# bmsSlave_cells.net
KiCad netlist of a schematic drawn in Altium Designer
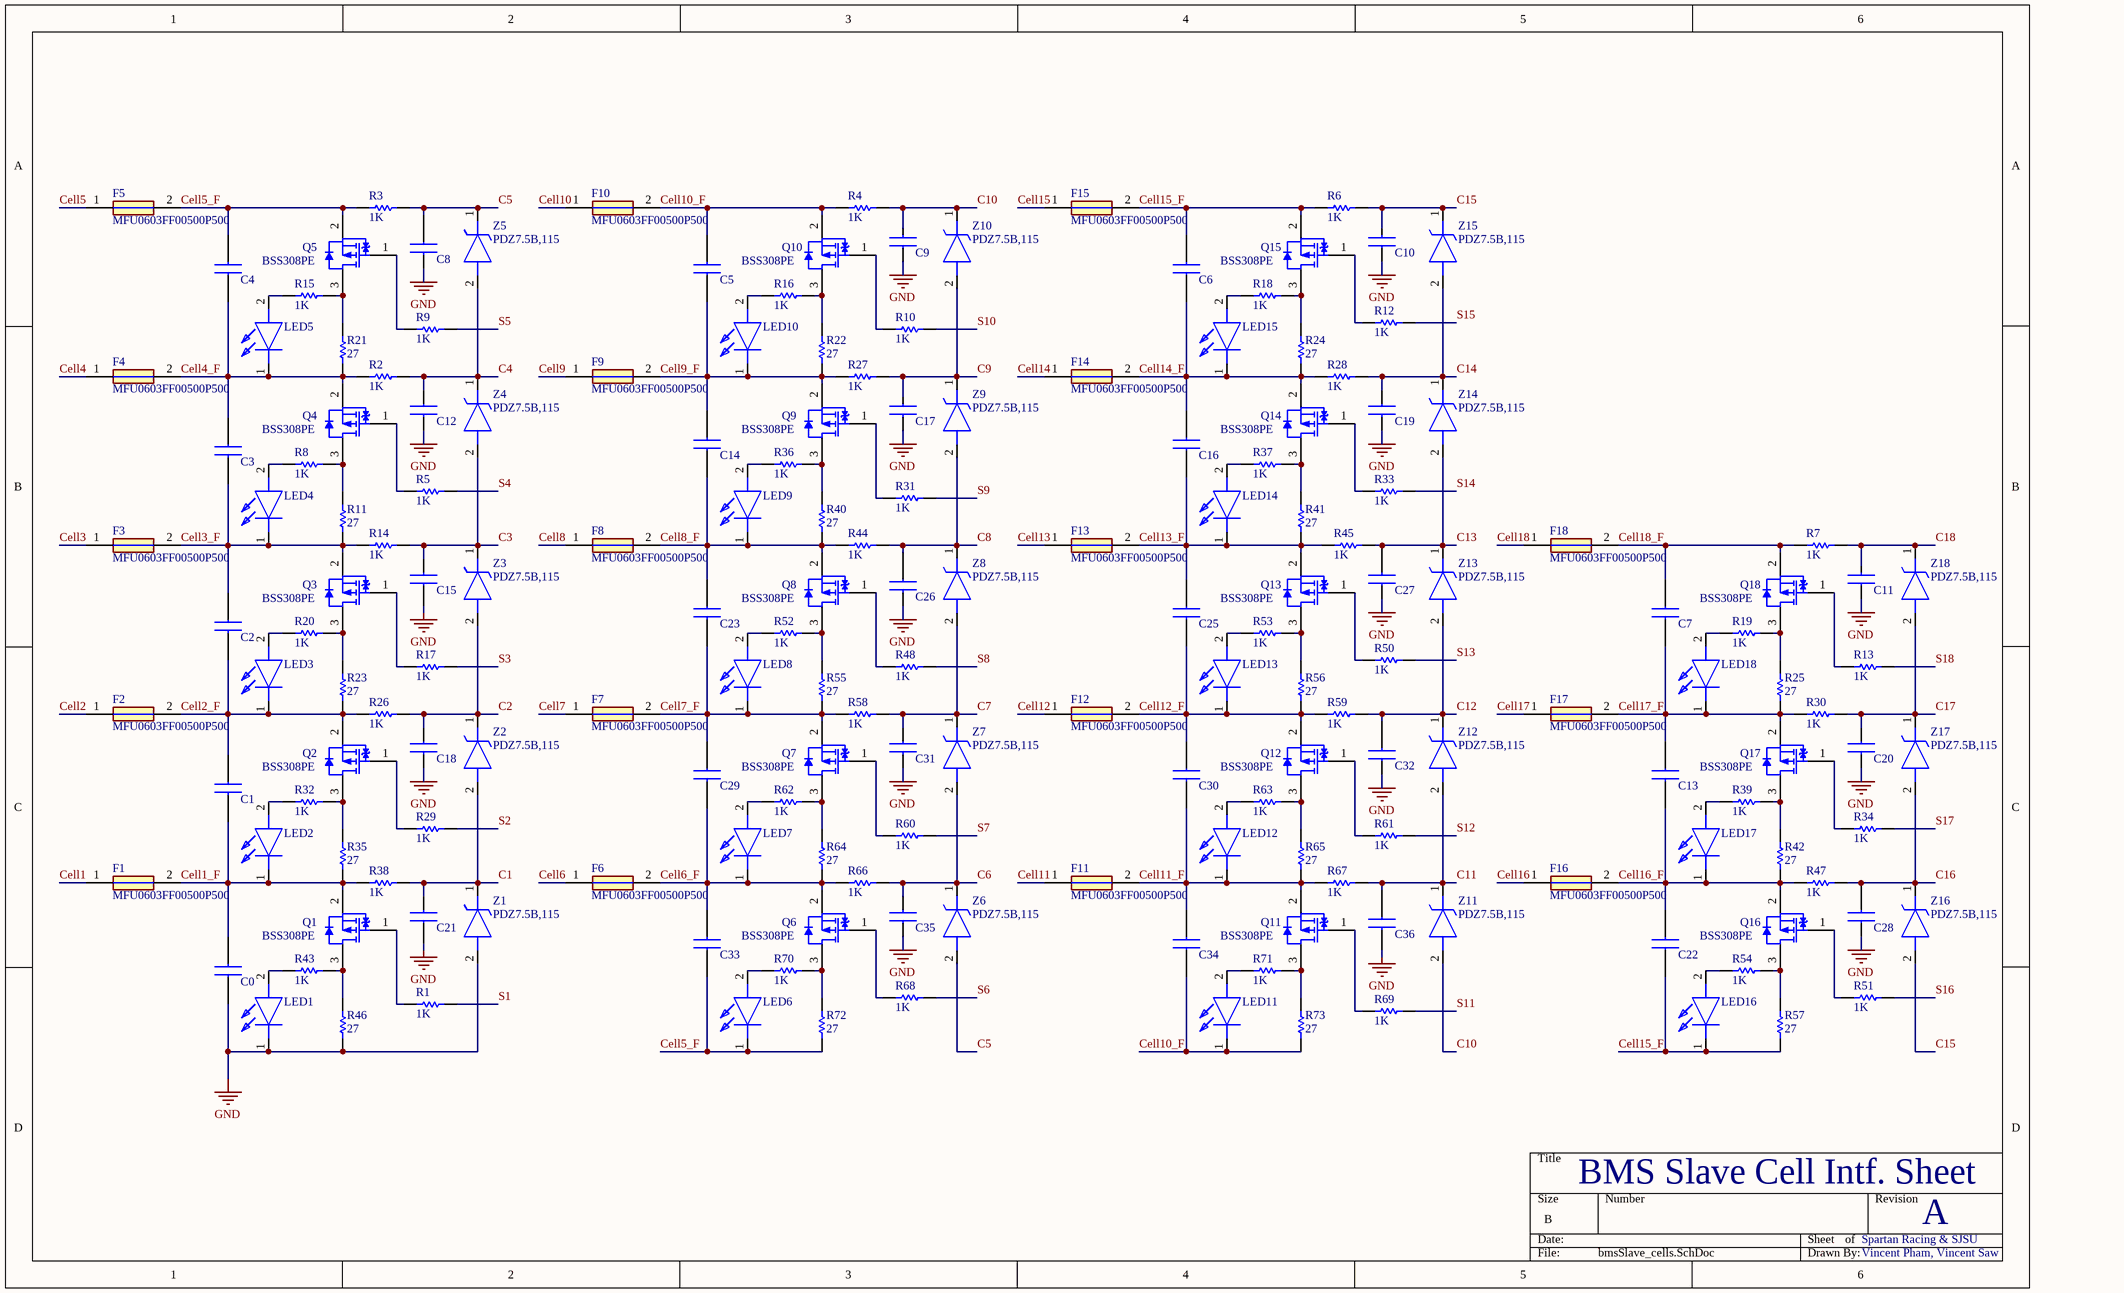
[diagram p0: bmsSlave_cells.SchDoc]

(export (version "E")
  (design (tool "Eeschema 10.0.6"))
  (components
    (comp (ref "C0")
      (value "885382207009")
      (footprint "C0603")
      (description "Multilayer Ceramic Chip Capacitor WCAP-CSST Series 0805 10000pF X7R0805103K100DFCT1S000")
      (fields (field (name "MOUSER PART NUMBER") "710-885382207009"))
      (libsource (lib "885382207009") (part "885382207009"))
    )
    (comp (ref "C1")
      (value "885382207009")
      (footprint "C0603")
      (description "Multilayer Ceramic Chip Capacitor WCAP-CSST Series 0805 10000pF X7R0805103K100DFCT1S000")
      (fields (field (name "MOUSER PART NUMBER") "710-885382207009"))
      (libsource (lib "885382207009") (part "885382207009"))
    )
    (comp (ref "C2")
      (value "885382207009")
      (footprint "C0603")
      (description "Multilayer Ceramic Chip Capacitor WCAP-CSST Series 0805 10000pF X7R0805103K100DFCT1S000")
      (fields (field (name "MOUSER PART NUMBER") "710-885382207009"))
      (libsource (lib "885382207009") (part "885382207009"))
    )
    (comp (ref "C3")
      (value "885382207009")
      (footprint "C0603")
      (description "Multilayer Ceramic Chip Capacitor WCAP-CSST Series 0805 10000pF X7R0805103K100DFCT1S000")
      (fields (field (name "MOUSER PART NUMBER") "710-885382207009"))
      (libsource (lib "885382207009") (part "885382207009"))
    )
    (comp (ref "C4")
      (value "885382207009")
      (footprint "C0603")
      (description "Multilayer Ceramic Chip Capacitor WCAP-CSST Series 0805 10000pF X7R0805103K100DFCT1S000")
      (fields (field (name "MOUSER PART NUMBER") "710-885382207009"))
      (libsource (lib "885382207009") (part "885382207009"))
    )
    (comp (ref "C5")
      (value "885382207009")
      (footprint "C0603")
      (description "Multilayer Ceramic Chip Capacitor WCAP-CSST Series 0805 10000pF X7R0805103K100DFCT1S000")
      (fields (field (name "MOUSER PART NUMBER") "710-885382207009"))
      (libsource (lib "885382207009") (part "885382207009"))
    )
    (comp (ref "C6")
      (value "885382207009")
      (footprint "C0603")
      (description "Multilayer Ceramic Chip Capacitor WCAP-CSST Series 0805 10000pF X7R0805103K100DFCT1S000")
      (fields (field (name "MOUSER PART NUMBER") "710-885382207009"))
      (libsource (lib "885382207009") (part "885382207009"))
    )
    (comp (ref "C7")
      (value "885382207009")
      (footprint "C0603")
      (description "Multilayer Ceramic Chip Capacitor WCAP-CSST Series 0805 10000pF X7R0805103K100DFCT1S000")
      (fields (field (name "MOUSER PART NUMBER") "710-885382207009"))
      (libsource (lib "885382207009") (part "885382207009"))
    )
    (comp (ref "C8")
      (value "885382207009")
      (footprint "C0603")
      (description "Multilayer Ceramic Chip Capacitor WCAP-CSST Series 0805 10000pF X7R0805103K100DFCT1S000")
      (fields (field (name "MOUSER PART NUMBER") "710-885382207009"))
      (libsource (lib "885382207009") (part "885382207009"))
    )
    (comp (ref "C9")
      (value "885382207009")
      (footprint "C0603")
      (description "Multilayer Ceramic Chip Capacitor WCAP-CSST Series 0805 10000pF X7R0805103K100DFCT1S000")
      (fields (field (name "MOUSER PART NUMBER") "710-885382207009"))
      (libsource (lib "885382207009") (part "885382207009"))
    )
    (comp (ref "C10")
      (value "885382207009")
      (footprint "C0603")
      (description "Multilayer Ceramic Chip Capacitor WCAP-CSST Series 0805 10000pF X7R0805103K100DFCT1S000")
      (fields (field (name "MOUSER PART NUMBER") "710-885382207009"))
      (libsource (lib "885382207009") (part "885382207009"))
    )
    (comp (ref "C11")
      (value "885382207009")
      (footprint "C0603")
      (description "Multilayer Ceramic Chip Capacitor WCAP-CSST Series 0805 10000pF X7R0805103K100DFCT1S000")
      (fields (field (name "MOUSER PART NUMBER") "710-885382207009"))
      (libsource (lib "885382207009") (part "885382207009"))
    )
    (comp (ref "C12")
      (value "885382207009")
      (footprint "C0603")
      (description "Multilayer Ceramic Chip Capacitor WCAP-CSST Series 0805 10000pF X7R0805103K100DFCT1S000")
      (fields (field (name "MOUSER PART NUMBER") "710-885382207009"))
      (libsource (lib "885382207009") (part "885382207009"))
    )
    (comp (ref "C13")
      (value "885382207009")
      (footprint "C0603")
      (description "Multilayer Ceramic Chip Capacitor WCAP-CSST Series 0805 10000pF X7R0805103K100DFCT1S000")
      (fields (field (name "MOUSER PART NUMBER") "710-885382207009"))
      (libsource (lib "885382207009") (part "885382207009"))
    )
    (comp (ref "C14")
      (value "885382207009")
      (footprint "C0603")
      (description "Multilayer Ceramic Chip Capacitor WCAP-CSST Series 0805 10000pF X7R0805103K100DFCT1S000")
      (fields (field (name "MOUSER PART NUMBER") "710-885382207009"))
      (libsource (lib "885382207009") (part "885382207009"))
    )
    (comp (ref "C15")
      (value "885382207009")
      (footprint "C0603")
      (description "Multilayer Ceramic Chip Capacitor WCAP-CSST Series 0805 10000pF X7R0805103K100DFCT1S000")
      (fields (field (name "MOUSER PART NUMBER") "710-885382207009"))
      (libsource (lib "885382207009") (part "885382207009"))
    )
    (comp (ref "C16")
      (value "885382207009")
      (footprint "C0603")
      (description "Multilayer Ceramic Chip Capacitor WCAP-CSST Series 0805 10000pF X7R0805103K100DFCT1S000")
      (fields (field (name "MOUSER PART NUMBER") "710-885382207009"))
      (libsource (lib "885382207009") (part "885382207009"))
    )
    (comp (ref "C17")
      (value "885382207009")
      (footprint "C0603")
      (description "Multilayer Ceramic Chip Capacitor WCAP-CSST Series 0805 10000pF X7R0805103K100DFCT1S000")
      (fields (field (name "MOUSER PART NUMBER") "710-885382207009"))
      (libsource (lib "885382207009") (part "885382207009"))
    )
    (comp (ref "C18")
      (value "885382207009")
      (footprint "C0603")
      (description "Multilayer Ceramic Chip Capacitor WCAP-CSST Series 0805 10000pF X7R0805103K100DFCT1S000")
      (fields (field (name "MOUSER PART NUMBER") "710-885382207009"))
      (libsource (lib "885382207009") (part "885382207009"))
    )
    (comp (ref "C19")
      (value "885382207009")
      (footprint "C0603")
      (description "Multilayer Ceramic Chip Capacitor WCAP-CSST Series 0805 10000pF X7R0805103K100DFCT1S000")
      (fields (field (name "MOUSER PART NUMBER") "710-885382207009"))
      (libsource (lib "885382207009") (part "885382207009"))
    )
    (comp (ref "C20")
      (value "885382207009")
      (footprint "C0603")
      (description "Multilayer Ceramic Chip Capacitor WCAP-CSST Series 0805 10000pF X7R0805103K100DFCT1S000")
      (fields (field (name "MOUSER PART NUMBER") "710-885382207009"))
      (libsource (lib "885382207009") (part "885382207009"))
    )
    (comp (ref "C21")
      (value "885382207009")
      (footprint "C0603")
      (description "Multilayer Ceramic Chip Capacitor WCAP-CSST Series 0805 10000pF X7R0805103K100DFCT1S000")
      (fields (field (name "MOUSER PART NUMBER") "710-885382207009"))
      (libsource (lib "885382207009") (part "885382207009"))
    )
    (comp (ref "C22")
      (value "885382207009")
      (footprint "C0603")
      (description "Multilayer Ceramic Chip Capacitor WCAP-CSST Series 0805 10000pF X7R0805103K100DFCT1S000")
      (fields (field (name "MOUSER PART NUMBER") "710-885382207009"))
      (libsource (lib "885382207009") (part "885382207009"))
    )
    (comp (ref "C23")
      (value "885382207009")
      (footprint "C0603")
      (description "Multilayer Ceramic Chip Capacitor WCAP-CSST Series 0805 10000pF X7R0805103K100DFCT1S000")
      (fields (field (name "MOUSER PART NUMBER") "710-885382207009"))
      (libsource (lib "885382207009") (part "885382207009"))
    )
    (comp (ref "C25")
      (value "885382207009")
      (footprint "C0603")
      (description "Multilayer Ceramic Chip Capacitor WCAP-CSST Series 0805 10000pF X7R0805103K100DFCT1S000")
      (fields (field (name "MOUSER PART NUMBER") "710-885382207009"))
      (libsource (lib "885382207009") (part "885382207009"))
    )
    (comp (ref "C26")
      (value "885382207009")
      (footprint "C0603")
      (description "Multilayer Ceramic Chip Capacitor WCAP-CSST Series 0805 10000pF X7R0805103K100DFCT1S000")
      (fields (field (name "MOUSER PART NUMBER") "710-885382207009"))
      (libsource (lib "885382207009") (part "885382207009"))
    )
    (comp (ref "C27")
      (value "885382207009")
      (footprint "C0603")
      (description "Multilayer Ceramic Chip Capacitor WCAP-CSST Series 0805 10000pF X7R0805103K100DFCT1S000")
      (fields (field (name "MOUSER PART NUMBER") "710-885382207009"))
      (libsource (lib "885382207009") (part "885382207009"))
    )
    (comp (ref "C28")
      (value "885382207009")
      (footprint "C0603")
      (description "Multilayer Ceramic Chip Capacitor WCAP-CSST Series 0805 10000pF X7R0805103K100DFCT1S000")
      (fields (field (name "MOUSER PART NUMBER") "710-885382207009"))
      (libsource (lib "885382207009") (part "885382207009"))
    )
    (comp (ref "C29")
      (value "885382207009")
      (footprint "C0603")
      (description "Multilayer Ceramic Chip Capacitor WCAP-CSST Series 0805 10000pF X7R0805103K100DFCT1S000")
      (fields (field (name "MOUSER PART NUMBER") "710-885382207009"))
      (libsource (lib "885382207009") (part "885382207009"))
    )
    (comp (ref "C30")
      (value "885382207009")
      (footprint "C0603")
      (description "Multilayer Ceramic Chip Capacitor WCAP-CSST Series 0805 10000pF X7R0805103K100DFCT1S000")
      (fields (field (name "MOUSER PART NUMBER") "710-885382207009"))
      (libsource (lib "885382207009") (part "885382207009"))
    )
    (comp (ref "C31")
      (value "885382207009")
      (footprint "C0603")
      (description "Multilayer Ceramic Chip Capacitor WCAP-CSST Series 0805 10000pF X7R0805103K100DFCT1S000")
      (fields (field (name "MOUSER PART NUMBER") "710-885382207009"))
      (libsource (lib "885382207009") (part "885382207009"))
    )
    (comp (ref "C32")
      (value "885382207009")
      (footprint "C0603")
      (description "Multilayer Ceramic Chip Capacitor WCAP-CSST Series 0805 10000pF X7R0805103K100DFCT1S000")
      (fields (field (name "MOUSER PART NUMBER") "710-885382207009"))
      (libsource (lib "885382207009") (part "885382207009"))
    )
    (comp (ref "C33")
      (value "885382207009")
      (footprint "C0603")
      (description "Multilayer Ceramic Chip Capacitor WCAP-CSST Series 0805 10000pF X7R0805103K100DFCT1S000")
      (fields (field (name "MOUSER PART NUMBER") "710-885382207009"))
      (libsource (lib "885382207009") (part "885382207009"))
    )
    (comp (ref "C34")
      (value "885382207009")
      (footprint "C0603")
      (description "Multilayer Ceramic Chip Capacitor WCAP-CSST Series 0805 10000pF X7R0805103K100DFCT1S000")
      (fields (field (name "MOUSER PART NUMBER") "710-885382207009"))
      (libsource (lib "885382207009") (part "885382207009"))
    )
    (comp (ref "C35")
      (value "885382207009")
      (footprint "C0603")
      (description "Multilayer Ceramic Chip Capacitor WCAP-CSST Series 0805 10000pF X7R0805103K100DFCT1S000")
      (fields (field (name "MOUSER PART NUMBER") "710-885382207009"))
      (libsource (lib "885382207009") (part "885382207009"))
    )
    (comp (ref "C36")
      (value "885382207009")
      (footprint "C0603")
      (description "Multilayer Ceramic Chip Capacitor WCAP-CSST Series 0805 10000pF X7R0805103K100DFCT1S000")
      (fields (field (name "MOUSER PART NUMBER") "710-885382207009"))
      (libsource (lib "885382207009") (part "885382207009"))
    )
    (comp (ref "F1")
      (value "MFU0603FF00500P500")
      (footprint "FUSC1608X55N")
      (description "Fuse")
      (fields (field (name "MOUSER PART NUMBER") "594-MFU0603-FF-0.5"))
      (libsource (lib "bmsSlave") (part "MFU0603FF00500P500"))
    )
    (comp (ref "F2")
      (value "MFU0603FF00500P500")
      (footprint "FUSC1608X55N")
      (description "Fuse")
      (fields (field (name "MOUSER PART NUMBER") "594-MFU0603-FF-0.5"))
      (libsource (lib "bmsSlave") (part "MFU0603FF00500P500"))
    )
    (comp (ref "F3")
      (value "MFU0603FF00500P500")
      (footprint "FUSC1608X55N")
      (description "Fuse")
      (fields (field (name "MOUSER PART NUMBER") "594-MFU0603-FF-0.5"))
      (libsource (lib "bmsSlave") (part "MFU0603FF00500P500"))
    )
    (comp (ref "F4")
      (value "MFU0603FF00500P500")
      (footprint "FUSC1608X55N")
      (description "Fuse")
      (fields (field (name "MOUSER PART NUMBER") "594-MFU0603-FF-0.5"))
      (libsource (lib "bmsSlave") (part "MFU0603FF00500P500"))
    )
    (comp (ref "F5")
      (value "MFU0603FF00500P500")
      (footprint "FUSC1608X55N")
      (description "Fuse")
      (fields (field (name "MOUSER PART NUMBER") "594-MFU0603-FF-0.5"))
      (libsource (lib "bmsSlave") (part "MFU0603FF00500P500"))
    )
    (comp (ref "F6")
      (value "MFU0603FF00500P500")
      (footprint "FUSC1608X55N")
      (description "Fuse")
      (fields (field (name "MOUSER PART NUMBER") "594-MFU0603-FF-0.5"))
      (libsource (lib "bmsSlave") (part "MFU0603FF00500P500"))
    )
    (comp (ref "F7")
      (value "MFU0603FF00500P500")
      (footprint "FUSC1608X55N")
      (description "Fuse")
      (fields (field (name "MOUSER PART NUMBER") "594-MFU0603-FF-0.5"))
      (libsource (lib "bmsSlave") (part "MFU0603FF00500P500"))
    )
    (comp (ref "F8")
      (value "MFU0603FF00500P500")
      (footprint "FUSC1608X55N")
      (description "Fuse")
      (fields (field (name "MOUSER PART NUMBER") "594-MFU0603-FF-0.5"))
      (libsource (lib "bmsSlave") (part "MFU0603FF00500P500"))
    )
    (comp (ref "F9")
      (value "MFU0603FF00500P500")
      (footprint "FUSC1608X55N")
      (description "Fuse")
      (fields (field (name "MOUSER PART NUMBER") "594-MFU0603-FF-0.5"))
      (libsource (lib "bmsSlave") (part "MFU0603FF00500P500"))
    )
    (comp (ref "F10")
      (value "MFU0603FF00500P500")
      (footprint "FUSC1608X55N")
      (description "Fuse")
      (fields (field (name "MOUSER PART NUMBER") "594-MFU0603-FF-0.5"))
      (libsource (lib "bmsSlave") (part "MFU0603FF00500P500"))
    )
    (comp (ref "F11")
      (value "MFU0603FF00500P500")
      (footprint "FUSC1608X55N")
      (description "Fuse")
      (fields (field (name "MOUSER PART NUMBER") "594-MFU0603-FF-0.5"))
      (libsource (lib "bmsSlave") (part "MFU0603FF00500P500"))
    )
    (comp (ref "F12")
      (value "MFU0603FF00500P500")
      (footprint "FUSC1608X55N")
      (description "Fuse")
      (fields (field (name "MOUSER PART NUMBER") "594-MFU0603-FF-0.5"))
      (libsource (lib "bmsSlave") (part "MFU0603FF00500P500"))
    )
    (comp (ref "F13")
      (value "MFU0603FF00500P500")
      (footprint "FUSC1608X55N")
      (description "Fuse")
      (fields (field (name "MOUSER PART NUMBER") "594-MFU0603-FF-0.5"))
      (libsource (lib "bmsSlave") (part "MFU0603FF00500P500"))
    )
    (comp (ref "F14")
      (value "MFU0603FF00500P500")
      (footprint "FUSC1608X55N")
      (description "Fuse")
      (fields (field (name "MOUSER PART NUMBER") "594-MFU0603-FF-0.5"))
      (libsource (lib "bmsSlave") (part "MFU0603FF00500P500"))
    )
    (comp (ref "F15")
      (value "MFU0603FF00500P500")
      (footprint "FUSC1608X55N")
      (description "Fuse")
      (fields (field (name "MOUSER PART NUMBER") "594-MFU0603-FF-0.5"))
      (libsource (lib "bmsSlave") (part "MFU0603FF00500P500"))
    )
    (comp (ref "F16")
      (value "MFU0603FF00500P500")
      (footprint "FUSC1608X55N")
      (description "Fuse")
      (fields (field (name "MOUSER PART NUMBER") "594-MFU0603-FF-0.5"))
      (libsource (lib "bmsSlave") (part "MFU0603FF00500P500"))
    )
    (comp (ref "F17")
      (value "MFU0603FF00500P500")
      (footprint "FUSC1608X55N")
      (description "Fuse")
      (fields (field (name "MOUSER PART NUMBER") "594-MFU0603-FF-0.5"))
      (libsource (lib "bmsSlave") (part "MFU0603FF00500P500"))
    )
    (comp (ref "F18")
      (value "MFU0603FF00500P500")
      (footprint "FUSC1608X55N")
      (description "Fuse")
      (fields (field (name "MOUSER PART NUMBER") "594-MFU0603-FF-0.5"))
      (libsource (lib "bmsSlave") (part "MFU0603FF00500P500"))
    )
    (comp (ref "LED1")
      (value "LS_L29K-G1H2-1")
      (footprint "SamacSys:LEDC1308X67N")
      (description "LED")
      (fields
        (field (name "MANUFACTURER_PART_NUMBER") "LS L29K-G1H2-1")
        (field (name "MOUSER PART NUMBER") "720-LSL29K-G1H2-1-Z")
      )
      (libsource (lib "*") (part "LS_L29K-G1H2-1"))
    )
    (comp (ref "LED2")
      (value "LS_L29K-G1H2-1")
      (footprint "SamacSys:LEDC1308X67N")
      (description "LED")
      (fields
        (field (name "MANUFACTURER_PART_NUMBER") "LS L29K-G1H2-1")
        (field (name "MOUSER PART NUMBER") "720-LSL29K-G1H2-1-Z")
      )
      (libsource (lib "*") (part "LS_L29K-G1H2-1"))
    )
    (comp (ref "LED3")
      (value "LS_L29K-G1H2-1")
      (footprint "SamacSys:LEDC1308X67N")
      (description "LED")
      (fields
        (field (name "MANUFACTURER_PART_NUMBER") "LS L29K-G1H2-1")
        (field (name "MOUSER PART NUMBER") "720-LSL29K-G1H2-1-Z")
      )
      (libsource (lib "*") (part "LS_L29K-G1H2-1"))
    )
    (comp (ref "LED4")
      (value "LS_L29K-G1H2-1")
      (footprint "SamacSys:LEDC1308X67N")
      (description "LED")
      (fields
        (field (name "MANUFACTURER_PART_NUMBER") "LS L29K-G1H2-1")
        (field (name "MOUSER PART NUMBER") "720-LSL29K-G1H2-1-Z")
      )
      (libsource (lib "*") (part "LS_L29K-G1H2-1"))
    )
    (comp (ref "LED5")
      (value "LS_L29K-G1H2-1")
      (footprint "SamacSys:LEDC1308X67N")
      (description "LED")
      (fields
        (field (name "MANUFACTURER_PART_NUMBER") "LS L29K-G1H2-1")
        (field (name "MOUSER PART NUMBER") "720-LSL29K-G1H2-1-Z")
      )
      (libsource (lib "*") (part "LS_L29K-G1H2-1"))
    )
    (comp (ref "LED6")
      (value "LS_L29K-G1H2-1")
      (footprint "SamacSys:LEDC1308X67N")
      (description "LED")
      (fields
        (field (name "MANUFACTURER_PART_NUMBER") "LS L29K-G1H2-1")
        (field (name "MOUSER PART NUMBER") "720-LSL29K-G1H2-1-Z")
      )
      (libsource (lib "*") (part "LS_L29K-G1H2-1"))
    )
    (comp (ref "LED7")
      (value "LS_L29K-G1H2-1")
      (footprint "SamacSys:LEDC1308X67N")
      (description "LED")
      (fields
        (field (name "MANUFACTURER_PART_NUMBER") "LS L29K-G1H2-1")
        (field (name "MOUSER PART NUMBER") "720-LSL29K-G1H2-1-Z")
      )
      (libsource (lib "*") (part "LS_L29K-G1H2-1"))
    )
    (comp (ref "LED8")
      (value "LS_L29K-G1H2-1")
      (footprint "SamacSys:LEDC1308X67N")
      (description "LED")
      (fields
        (field (name "MANUFACTURER_PART_NUMBER") "LS L29K-G1H2-1")
        (field (name "MOUSER PART NUMBER") "720-LSL29K-G1H2-1-Z")
      )
      (libsource (lib "*") (part "LS_L29K-G1H2-1"))
    )
    (comp (ref "LED9")
      (value "LS_L29K-G1H2-1")
      (footprint "SamacSys:LEDC1308X67N")
      (description "LED")
      (fields
        (field (name "MANUFACTURER_PART_NUMBER") "LS L29K-G1H2-1")
        (field (name "MOUSER PART NUMBER") "720-LSL29K-G1H2-1-Z")
      )
      (libsource (lib "*") (part "LS_L29K-G1H2-1"))
    )
    (comp (ref "LED10")
      (value "LS_L29K-G1H2-1")
      (footprint "SamacSys:LEDC1308X67N")
      (description "LED")
      (fields
        (field (name "MANUFACTURER_PART_NUMBER") "LS L29K-G1H2-1")
        (field (name "MOUSER PART NUMBER") "720-LSL29K-G1H2-1-Z")
      )
      (libsource (lib "*") (part "LS_L29K-G1H2-1"))
    )
    (comp (ref "LED11")
      (value "LS_L29K-G1H2-1")
      (footprint "SamacSys:LEDC1308X67N")
      (description "LED")
      (fields
        (field (name "MANUFACTURER_PART_NUMBER") "LS L29K-G1H2-1")
        (field (name "MOUSER PART NUMBER") "720-LSL29K-G1H2-1-Z")
      )
      (libsource (lib "*") (part "LS_L29K-G1H2-1"))
    )
    (comp (ref "LED12")
      (value "LS_L29K-G1H2-1")
      (footprint "SamacSys:LEDC1308X67N")
      (description "LED")
      (fields
        (field (name "MANUFACTURER_PART_NUMBER") "LS L29K-G1H2-1")
        (field (name "MOUSER PART NUMBER") "720-LSL29K-G1H2-1-Z")
      )
      (libsource (lib "*") (part "LS_L29K-G1H2-1"))
    )
    (comp (ref "LED13")
      (value "LS_L29K-G1H2-1")
      (footprint "SamacSys:LEDC1308X67N")
      (description "LED")
      (fields
        (field (name "MANUFACTURER_PART_NUMBER") "LS L29K-G1H2-1")
        (field (name "MOUSER PART NUMBER") "720-LSL29K-G1H2-1-Z")
      )
      (libsource (lib "*") (part "LS_L29K-G1H2-1"))
    )
    (comp (ref "LED14")
      (value "LS_L29K-G1H2-1")
      (footprint "SamacSys:LEDC1308X67N")
      (description "LED")
      (fields
        (field (name "MANUFACTURER_PART_NUMBER") "LS L29K-G1H2-1")
        (field (name "MOUSER PART NUMBER") "720-LSL29K-G1H2-1-Z")
      )
      (libsource (lib "*") (part "LS_L29K-G1H2-1"))
    )
    (comp (ref "LED15")
      (value "LS_L29K-G1H2-1")
      (footprint "SamacSys:LEDC1308X67N")
      (description "LED")
      (fields
        (field (name "MANUFACTURER_PART_NUMBER") "LS L29K-G1H2-1")
        (field (name "MOUSER PART NUMBER") "720-LSL29K-G1H2-1-Z")
      )
      (libsource (lib "*") (part "LS_L29K-G1H2-1"))
    )
    (comp (ref "LED16")
      (value "LS_L29K-G1H2-1")
      (footprint "SamacSys:LEDC1308X67N")
      (description "LED")
      (fields
        (field (name "MANUFACTURER_PART_NUMBER") "LS L29K-G1H2-1")
        (field (name "MOUSER PART NUMBER") "720-LSL29K-G1H2-1-Z")
      )
      (libsource (lib "*") (part "LS_L29K-G1H2-1"))
    )
    (comp (ref "LED17")
      (value "LS_L29K-G1H2-1")
      (footprint "SamacSys:LEDC1308X67N")
      (description "LED")
      (fields
        (field (name "MANUFACTURER_PART_NUMBER") "LS L29K-G1H2-1")
        (field (name "MOUSER PART NUMBER") "720-LSL29K-G1H2-1-Z")
      )
      (libsource (lib "*") (part "LS_L29K-G1H2-1"))
    )
    (comp (ref "LED18")
      (value "LS_L29K-G1H2-1")
      (footprint "SamacSys:LEDC1308X67N")
      (description "LED")
      (fields
        (field (name "MANUFACTURER_PART_NUMBER") "LS L29K-G1H2-1")
        (field (name "MOUSER PART NUMBER") "720-LSL29K-G1H2-1-Z")
      )
      (libsource (lib "*") (part "LS_L29K-G1H2-1"))
    )
    (comp (ref "Q1")
      (value "BSS308PE")
      (footprint "INF-PG-SOT23_L")
      (fields (field (name "MANUFACTURER") "Infineon"))
      (libsource (lib "Altium Content Vault") (part "INF-BSS3XXPE-PG-SOT23-3"))
    )
    (comp (ref "Q2")
      (value "BSS308PE")
      (footprint "INF-PG-SOT23_L")
      (fields (field (name "MANUFACTURER") "Infineon"))
      (libsource (lib "Altium Content Vault") (part "INF-BSS3XXPE-PG-SOT23-3"))
    )
    (comp (ref "Q3")
      (value "BSS308PE")
      (footprint "INF-PG-SOT23_L")
      (fields (field (name "MANUFACTURER") "Infineon"))
      (libsource (lib "Altium Content Vault") (part "INF-BSS3XXPE-PG-SOT23-3"))
    )
    (comp (ref "Q4")
      (value "BSS308PE")
      (footprint "INF-PG-SOT23_L")
      (fields (field (name "MANUFACTURER") "Infineon"))
      (libsource (lib "Altium Content Vault") (part "INF-BSS3XXPE-PG-SOT23-3"))
    )
    (comp (ref "Q5")
      (value "BSS308PE")
      (footprint "INF-PG-SOT23_L")
      (fields (field (name "MANUFACTURER") "Infineon"))
      (libsource (lib "Altium Content Vault") (part "INF-BSS3XXPE-PG-SOT23-3"))
    )
    (comp (ref "Q6")
      (value "BSS308PE")
      (footprint "INF-PG-SOT23_L")
      (fields (field (name "MANUFACTURER") "Infineon"))
      (libsource (lib "Altium Content Vault") (part "INF-BSS3XXPE-PG-SOT23-3"))
    )
    (comp (ref "Q7")
      (value "BSS308PE")
      (footprint "INF-PG-SOT23_L")
      (fields (field (name "MANUFACTURER") "Infineon"))
      (libsource (lib "Altium Content Vault") (part "INF-BSS3XXPE-PG-SOT23-3"))
    )
    (comp (ref "Q8")
      (value "BSS308PE")
      (footprint "INF-PG-SOT23_L")
      (fields (field (name "MANUFACTURER") "Infineon"))
      (libsource (lib "Altium Content Vault") (part "INF-BSS3XXPE-PG-SOT23-3"))
    )
    (comp (ref "Q9")
      (value "BSS308PE")
      (footprint "INF-PG-SOT23_L")
      (fields (field (name "MANUFACTURER") "Infineon"))
      (libsource (lib "Altium Content Vault") (part "INF-BSS3XXPE-PG-SOT23-3"))
    )
    (comp (ref "Q10")
      (value "BSS308PE")
      (footprint "INF-PG-SOT23_L")
      (fields (field (name "MANUFACTURER") "Infineon"))
      (libsource (lib "Altium Content Vault") (part "INF-BSS3XXPE-PG-SOT23-3"))
    )
    (comp (ref "Q11")
      (value "BSS308PE")
      (footprint "INF-PG-SOT23_L")
      (fields (field (name "MANUFACTURER") "Infineon"))
      (libsource (lib "Altium Content Vault") (part "INF-BSS3XXPE-PG-SOT23-3"))
    )
    (comp (ref "Q12")
      (value "BSS308PE")
      (footprint "INF-PG-SOT23_L")
      (fields (field (name "MANUFACTURER") "Infineon"))
      (libsource (lib "Altium Content Vault") (part "INF-BSS3XXPE-PG-SOT23-3"))
    )
    (comp (ref "Q13")
      (value "BSS308PE")
      (footprint "INF-PG-SOT23_L")
      (fields (field (name "MANUFACTURER") "Infineon"))
      (libsource (lib "Altium Content Vault") (part "INF-BSS3XXPE-PG-SOT23-3"))
    )
    (comp (ref "Q14")
      (value "BSS308PE")
      (footprint "INF-PG-SOT23_L")
      (fields (field (name "MANUFACTURER") "Infineon"))
      (libsource (lib "Altium Content Vault") (part "INF-BSS3XXPE-PG-SOT23-3"))
    )
    (comp (ref "Q15")
      (value "BSS308PE")
      (footprint "INF-PG-SOT23_L")
      (fields (field (name "MANUFACTURER") "Infineon"))
      (libsource (lib "Altium Content Vault") (part "INF-BSS3XXPE-PG-SOT23-3"))
    )
    (comp (ref "Q16")
      (value "BSS308PE")
      (footprint "INF-PG-SOT23_L")
      (fields (field (name "MANUFACTURER") "Infineon"))
      (libsource (lib "Altium Content Vault") (part "INF-BSS3XXPE-PG-SOT23-3"))
    )
    (comp (ref "Q17")
      (value "BSS308PE")
      (footprint "INF-PG-SOT23_L")
      (fields (field (name "MANUFACTURER") "Infineon"))
      (libsource (lib "Altium Content Vault") (part "INF-BSS3XXPE-PG-SOT23-3"))
    )
    (comp (ref "Q18")
      (value "BSS308PE")
      (footprint "INF-PG-SOT23_L")
      (fields (field (name "MANUFACTURER") "Infineon"))
      (libsource (lib "Altium Content Vault") (part "INF-BSS3XXPE-PG-SOT23-3"))
    )
    (comp (ref "R1")
      (value "1K")
      (footprint "R0603")
      (description "Resistor")
      (libsource (lib "Simulation Generic Components") (part "Resistor"))
    )
    (comp (ref "R2")
      (value "1K")
      (footprint "R0603")
      (description "Resistor")
      (libsource (lib "Simulation Generic Components") (part "Resistor"))
    )
    (comp (ref "R3")
      (value "1K")
      (footprint "R0603")
      (description "Resistor")
      (libsource (lib "Simulation Generic Components") (part "Resistor"))
    )
    (comp (ref "R4")
      (value "1K")
      (footprint "R0603")
      (description "Resistor")
      (libsource (lib "Simulation Generic Components") (part "Resistor"))
    )
    (comp (ref "R5")
      (value "1K")
      (footprint "R0603")
      (description "Resistor")
      (libsource (lib "Simulation Generic Components") (part "Resistor"))
    )
    (comp (ref "R6")
      (value "1K")
      (footprint "R0603")
      (description "Resistor")
      (libsource (lib "Simulation Generic Components") (part "Resistor"))
    )
    (comp (ref "R7")
      (value "1K")
      (footprint "R0603")
      (description "Resistor")
      (libsource (lib "Simulation Generic Components") (part "Resistor"))
    )
    (comp (ref "R8")
      (value "1K")
      (footprint "R0603")
      (description "Resistor")
      (libsource (lib "Simulation Generic Components") (part "Resistor"))
    )
    (comp (ref "R9")
      (value "1K")
      (footprint "R0603")
      (description "Resistor")
      (libsource (lib "Simulation Generic Components") (part "Resistor"))
    )
    (comp (ref "R10")
      (value "1K")
      (footprint "R0603")
      (description "Resistor")
      (libsource (lib "Simulation Generic Components") (part "Resistor"))
    )
    (comp (ref "R11")
      (value "27")
      (footprint "R2512")
      (description "Resistor")
      (libsource (lib "Simulation Generic Components") (part "Resistor"))
    )
    (comp (ref "R12")
      (value "1K")
      (footprint "R0603")
      (description "Resistor")
      (libsource (lib "Simulation Generic Components") (part "Resistor"))
    )
    (comp (ref "R13")
      (value "1K")
      (footprint "R0603")
      (description "Resistor")
      (libsource (lib "Simulation Generic Components") (part "Resistor"))
    )
    (comp (ref "R14")
      (value "1K")
      (footprint "R0603")
      (description "Resistor")
      (libsource (lib "Simulation Generic Components") (part "Resistor"))
    )
    (comp (ref "R15")
      (value "1K")
      (footprint "R0603")
      (description "Resistor")
      (libsource (lib "Simulation Generic Components") (part "Resistor"))
    )
    (comp (ref "R16")
      (value "1K")
      (footprint "R0603")
      (description "Resistor")
      (libsource (lib "Simulation Generic Components") (part "Resistor"))
    )
    (comp (ref "R17")
      (value "1K")
      (footprint "R0603")
      (description "Resistor")
      (libsource (lib "Simulation Generic Components") (part "Resistor"))
    )
    (comp (ref "R18")
      (value "1K")
      (footprint "R0603")
      (description "Resistor")
      (libsource (lib "Simulation Generic Components") (part "Resistor"))
    )
    (comp (ref "R19")
      (value "1K")
      (footprint "R0603")
      (description "Resistor")
      (libsource (lib "Simulation Generic Components") (part "Resistor"))
    )
    (comp (ref "R20")
      (value "1K")
      (footprint "R0603")
      (description "Resistor")
      (libsource (lib "Simulation Generic Components") (part "Resistor"))
    )
    (comp (ref "R21")
      (value "27")
      (footprint "R2512")
      (description "Resistor")
      (libsource (lib "Simulation Generic Components") (part "Resistor"))
    )
    (comp (ref "R22")
      (value "27")
      (footprint "R2512")
      (description "Resistor")
      (libsource (lib "Simulation Generic Components") (part "Resistor"))
    )
    (comp (ref "R23")
      (value "27")
      (footprint "R2512")
      (description "Resistor")
      (libsource (lib "Simulation Generic Components") (part "Resistor"))
    )
    (comp (ref "R24")
      (value "27")
      (footprint "R2512")
      (description "Resistor")
      (libsource (lib "Simulation Generic Components") (part "Resistor"))
    )
    (comp (ref "R25")
      (value "27")
      (footprint "R2512")
      (description "Resistor")
      (libsource (lib "Simulation Generic Components") (part "Resistor"))
    )
    (comp (ref "R26")
      (value "1K")
      (footprint "R0603")
      (description "Resistor")
      (libsource (lib "Simulation Generic Components") (part "Resistor"))
    )
    (comp (ref "R27")
      (value "1K")
      (footprint "R0603")
      (description "Resistor")
      (libsource (lib "Simulation Generic Components") (part "Resistor"))
    )
    (comp (ref "R28")
      (value "1K")
      (footprint "R0603")
      (description "Resistor")
      (libsource (lib "Simulation Generic Components") (part "Resistor"))
    )
    (comp (ref "R29")
      (value "1K")
      (footprint "R0603")
      (description "Resistor")
      (libsource (lib "Simulation Generic Components") (part "Resistor"))
    )
    (comp (ref "R30")
      (value "1K")
      (footprint "R0603")
      (description "Resistor")
      (libsource (lib "Simulation Generic Components") (part "Resistor"))
    )
    (comp (ref "R31")
      (value "1K")
      (footprint "R0603")
      (description "Resistor")
      (libsource (lib "Simulation Generic Components") (part "Resistor"))
    )
    (comp (ref "R32")
      (value "1K")
      (footprint "R0603")
      (description "Resistor")
      (libsource (lib "Simulation Generic Components") (part "Resistor"))
    )
    (comp (ref "R33")
      (value "1K")
      (footprint "R0603")
      (description "Resistor")
      (libsource (lib "Simulation Generic Components") (part "Resistor"))
    )
    (comp (ref "R34")
      (value "1K")
      (footprint "R0603")
      (description "Resistor")
      (libsource (lib "Simulation Generic Components") (part "Resistor"))
    )
    (comp (ref "R35")
      (value "27")
      (footprint "R2512")
      (description "Resistor")
      (libsource (lib "Simulation Generic Components") (part "Resistor"))
    )
    (comp (ref "R36")
      (value "1K")
      (footprint "R0603")
      (description "Resistor")
      (libsource (lib "Simulation Generic Components") (part "Resistor"))
    )
    (comp (ref "R37")
      (value "1K")
      (footprint "R0603")
      (description "Resistor")
      (libsource (lib "Simulation Generic Components") (part "Resistor"))
    )
    (comp (ref "R38")
      (value "1K")
      (footprint "R0603")
      (description "Resistor")
      (libsource (lib "Simulation Generic Components") (part "Resistor"))
    )
    (comp (ref "R39")
      (value "1K")
      (footprint "R0603")
      (description "Resistor")
      (libsource (lib "Simulation Generic Components") (part "Resistor"))
    )
    (comp (ref "R40")
      (value "27")
      (footprint "R2512")
      (description "Resistor")
      (libsource (lib "Simulation Generic Components") (part "Resistor"))
    )
    (comp (ref "R41")
      (value "27")
      (footprint "R2512")
      (description "Resistor")
      (libsource (lib "Simulation Generic Components") (part "Resistor"))
    )
    (comp (ref "R42")
      (value "27")
      (footprint "R2512")
      (description "Resistor")
      (libsource (lib "Simulation Generic Components") (part "Resistor"))
    )
    (comp (ref "R43")
      (value "1K")
      (footprint "R0603")
      (description "Resistor")
      (libsource (lib "Simulation Generic Components") (part "Resistor"))
    )
    (comp (ref "R44")
      (value "1K")
      (footprint "R0603")
      (description "Resistor")
      (libsource (lib "Simulation Generic Components") (part "Resistor"))
    )
    (comp (ref "R45")
      (value "1K")
      (footprint "R0603")
      (description "Resistor")
      (libsource (lib "Simulation Generic Components") (part "Resistor"))
    )
    (comp (ref "R46")
      (value "27")
      (footprint "R2512")
      (description "Resistor")
      (libsource (lib "Simulation Generic Components") (part "Resistor"))
    )
    (comp (ref "R47")
      (value "1K")
      (footprint "R0603")
      (description "Resistor")
      (libsource (lib "Simulation Generic Components") (part "Resistor"))
    )
    (comp (ref "R48")
      (value "1K")
      (footprint "R0603")
      (description "Resistor")
      (libsource (lib "Simulation Generic Components") (part "Resistor"))
    )
    (comp (ref "R50")
      (value "1K")
      (footprint "R0603")
      (description "Resistor")
      (libsource (lib "Simulation Generic Components") (part "Resistor"))
    )
    (comp (ref "R51")
      (value "1K")
      (footprint "R0603")
      (description "Resistor")
      (libsource (lib "Simulation Generic Components") (part "Resistor"))
    )
    (comp (ref "R52")
      (value "1K")
      (footprint "R0603")
      (description "Resistor")
      (libsource (lib "Simulation Generic Components") (part "Resistor"))
    )
    (comp (ref "R53")
      (value "1K")
      (footprint "R0603")
      (description "Resistor")
      (libsource (lib "Simulation Generic Components") (part "Resistor"))
    )
    (comp (ref "R54")
      (value "1K")
      (footprint "R0603")
      (description "Resistor")
      (libsource (lib "Simulation Generic Components") (part "Resistor"))
    )
    (comp (ref "R55")
      (value "27")
      (footprint "R2512")
      (description "Resistor")
      (libsource (lib "Simulation Generic Components") (part "Resistor"))
    )
    (comp (ref "R56")
      (value "27")
      (footprint "R2512")
      (description "Resistor")
      (libsource (lib "Simulation Generic Components") (part "Resistor"))
    )
    (comp (ref "R57")
      (value "27")
      (footprint "R2512")
      (description "Resistor")
      (libsource (lib "Simulation Generic Components") (part "Resistor"))
    )
    (comp (ref "R58")
      (value "1K")
      (footprint "R0603")
      (description "Resistor")
      (libsource (lib "Simulation Generic Components") (part "Resistor"))
    )
    (comp (ref "R59")
      (value "1K")
      (footprint "R0603")
      (description "Resistor")
      (libsource (lib "Simulation Generic Components") (part "Resistor"))
    )
    (comp (ref "R60")
      (value "1K")
      (footprint "R0603")
      (description "Resistor")
      (libsource (lib "Simulation Generic Components") (part "Resistor"))
    )
    (comp (ref "R61")
      (value "1K")
      (footprint "R0603")
      (description "Resistor")
      (libsource (lib "Simulation Generic Components") (part "Resistor"))
    )
    (comp (ref "R62")
      (value "1K")
      (footprint "R0603")
      (description "Resistor")
      (libsource (lib "Simulation Generic Components") (part "Resistor"))
    )
    (comp (ref "R63")
      (value "1K")
      (footprint "R0603")
      (description "Resistor")
      (libsource (lib "Simulation Generic Components") (part "Resistor"))
    )
    (comp (ref "R64")
      (value "27")
      (footprint "R2512")
      (description "Resistor")
      (libsource (lib "Simulation Generic Components") (part "Resistor"))
    )
    (comp (ref "R65")
      (value "27")
      (footprint "R2512")
      (description "Resistor")
      (libsource (lib "Simulation Generic Components") (part "Resistor"))
    )
    (comp (ref "R66")
      (value "1K")
      (footprint "R0603")
      (description "Resistor")
      (libsource (lib "Simulation Generic Components") (part "Resistor"))
    )
    (comp (ref "R67")
      (value "1K")
      (footprint "R0603")
      (description "Resistor")
      (libsource (lib "Simulation Generic Components") (part "Resistor"))
    )
    (comp (ref "R68")
      (value "1K")
      (footprint "R0603")
      (description "Resistor")
      (libsource (lib "Simulation Generic Components") (part "Resistor"))
    )
    (comp (ref "R69")
      (value "1K")
      (footprint "R0603")
      (description "Resistor")
      (libsource (lib "Simulation Generic Components") (part "Resistor"))
    )
    (comp (ref "R70")
      (value "1K")
      (footprint "R0603")
      (description "Resistor")
      (libsource (lib "Simulation Generic Components") (part "Resistor"))
    )
    (comp (ref "R71")
      (value "1K")
      (footprint "R0603")
      (description "Resistor")
      (libsource (lib "Simulation Generic Components") (part "Resistor"))
    )
    (comp (ref "R72")
      (value "27")
      (footprint "R2512")
      (description "Resistor")
      (libsource (lib "Simulation Generic Components") (part "Resistor"))
    )
    (comp (ref "R73")
      (value "27")
      (footprint "R2512")
      (description "Resistor")
      (libsource (lib "Simulation Generic Components") (part "Resistor"))
    )
    (comp (ref "Z1")
      (value "PDZ7.5B,115")
      (footprint "SamacSys:SOD2512X110N")
      (description "Zener Diode")
      (fields (field (name "MOUSER PART NUMBER") "771-PDZ75B115"))
      (libsource (lib "*") (part "PDZ7.5B,115"))
    )
    (comp (ref "Z2")
      (value "PDZ7.5B,115")
      (footprint "SamacSys:SOD2512X110N")
      (description "Zener Diode")
      (fields (field (name "MOUSER PART NUMBER") "771-PDZ75B115"))
      (libsource (lib "*") (part "PDZ7.5B,115"))
    )
    (comp (ref "Z3")
      (value "PDZ7.5B,115")
      (footprint "SamacSys:SOD2512X110N")
      (description "Zener Diode")
      (fields (field (name "MOUSER PART NUMBER") "771-PDZ75B115"))
      (libsource (lib "*") (part "PDZ7.5B,115"))
    )
    (comp (ref "Z4")
      (value "PDZ7.5B,115")
      (footprint "SamacSys:SOD2512X110N")
      (description "Zener Diode")
      (fields (field (name "MOUSER PART NUMBER") "771-PDZ75B115"))
      (libsource (lib "*") (part "PDZ7.5B,115"))
    )
    (comp (ref "Z5")
      (value "PDZ7.5B,115")
      (footprint "SamacSys:SOD2512X110N")
      (description "Zener Diode")
      (fields (field (name "MOUSER PART NUMBER") "771-PDZ75B115"))
      (libsource (lib "*") (part "PDZ7.5B,115"))
    )
    (comp (ref "Z6")
      (value "PDZ7.5B,115")
      (footprint "SamacSys:SOD2512X110N")
      (description "Zener Diode")
      (fields (field (name "MOUSER PART NUMBER") "771-PDZ75B115"))
      (libsource (lib "*") (part "PDZ7.5B,115"))
    )
    (comp (ref "Z7")
      (value "PDZ7.5B,115")
      (footprint "SamacSys:SOD2512X110N")
      (description "Zener Diode")
      (fields (field (name "MOUSER PART NUMBER") "771-PDZ75B115"))
      (libsource (lib "*") (part "PDZ7.5B,115"))
    )
    (comp (ref "Z8")
      (value "PDZ7.5B,115")
      (footprint "SamacSys:SOD2512X110N")
      (description "Zener Diode")
      (fields (field (name "MOUSER PART NUMBER") "771-PDZ75B115"))
      (libsource (lib "*") (part "PDZ7.5B,115"))
    )
    (comp (ref "Z9")
      (value "PDZ7.5B,115")
      (footprint "SamacSys:SOD2512X110N")
      (description "Zener Diode")
      (fields (field (name "MOUSER PART NUMBER") "771-PDZ75B115"))
      (libsource (lib "*") (part "PDZ7.5B,115"))
    )
    (comp (ref "Z10")
      (value "PDZ7.5B,115")
      (footprint "SamacSys:SOD2512X110N")
      (description "Zener Diode")
      (fields (field (name "MOUSER PART NUMBER") "771-PDZ75B115"))
      (libsource (lib "*") (part "PDZ7.5B,115"))
    )
    (comp (ref "Z11")
      (value "PDZ7.5B,115")
      (footprint "SamacSys:SOD2512X110N")
      (description "Zener Diode")
      (fields (field (name "MOUSER PART NUMBER") "771-PDZ75B115"))
      (libsource (lib "*") (part "PDZ7.5B,115"))
    )
    (comp (ref "Z12")
      (value "PDZ7.5B,115")
      (footprint "SamacSys:SOD2512X110N")
      (description "Zener Diode")
      (fields (field (name "MOUSER PART NUMBER") "771-PDZ75B115"))
      (libsource (lib "*") (part "PDZ7.5B,115"))
    )
    (comp (ref "Z13")
      (value "PDZ7.5B,115")
      (footprint "SamacSys:SOD2512X110N")
      (description "Zener Diode")
      (fields (field (name "MOUSER PART NUMBER") "771-PDZ75B115"))
      (libsource (lib "*") (part "PDZ7.5B,115"))
    )
    (comp (ref "Z14")
      (value "PDZ7.5B,115")
      (footprint "SamacSys:SOD2512X110N")
      (description "Zener Diode")
      (fields (field (name "MOUSER PART NUMBER") "771-PDZ75B115"))
      (libsource (lib "*") (part "PDZ7.5B,115"))
    )
    (comp (ref "Z15")
      (value "PDZ7.5B,115")
      (footprint "SamacSys:SOD2512X110N")
      (description "Zener Diode")
      (fields (field (name "MOUSER PART NUMBER") "771-PDZ75B115"))
      (libsource (lib "*") (part "PDZ7.5B,115"))
    )
    (comp (ref "Z16")
      (value "PDZ7.5B,115")
      (footprint "SamacSys:SOD2512X110N")
      (description "Zener Diode")
      (fields (field (name "MOUSER PART NUMBER") "771-PDZ75B115"))
      (libsource (lib "*") (part "PDZ7.5B,115"))
    )
    (comp (ref "Z17")
      (value "PDZ7.5B,115")
      (footprint "SamacSys:SOD2512X110N")
      (description "Zener Diode")
      (fields (field (name "MOUSER PART NUMBER") "771-PDZ75B115"))
      (libsource (lib "*") (part "PDZ7.5B,115"))
    )
    (comp (ref "Z18")
      (value "PDZ7.5B,115")
      (footprint "SamacSys:SOD2512X110N")
      (description "Zener Diode")
      (fields (field (name "MOUSER PART NUMBER") "771-PDZ75B115"))
      (libsource (lib "*") (part "PDZ7.5B,115"))
    )
  )
  (nets
    (net (code "1") (name "/C1") (class "Default")
      (node (ref "C21") (pin "2") (pinfunction "2_2") (pintype "passive"))
      (node (ref "R38") (pin "1") (pinfunction "1_1") (pintype "passive"))
      (node (ref "Z1") (pin "1") (pinfunction "K_1") (pintype "passive"))
      (node (ref "Z2") (pin "2") (pinfunction "A_2") (pintype "passive"))
    )
    (net (code "2") (name "/C2") (class "Default")
      (node (ref "C18") (pin "2") (pinfunction "2_2") (pintype "passive"))
      (node (ref "R26") (pin "1") (pinfunction "1_1") (pintype "passive"))
      (node (ref "Z2") (pin "1") (pinfunction "K_1") (pintype "passive"))
      (node (ref "Z3") (pin "2") (pinfunction "A_2") (pintype "passive"))
    )
    (net (code "3") (name "/C3") (class "Default")
      (node (ref "C15") (pin "2") (pinfunction "2_2") (pintype "passive"))
      (node (ref "R14") (pin "1") (pinfunction "1_1") (pintype "passive"))
      (node (ref "Z3") (pin "1") (pinfunction "K_1") (pintype "passive"))
      (node (ref "Z4") (pin "2") (pinfunction "A_2") (pintype "passive"))
    )
    (net (code "4") (name "/C4") (class "Default")
      (node (ref "C12") (pin "2") (pinfunction "2_2") (pintype "passive"))
      (node (ref "R2") (pin "1") (pinfunction "1_1") (pintype "passive"))
      (node (ref "Z4") (pin "1") (pinfunction "K_1") (pintype "passive"))
      (node (ref "Z5") (pin "2") (pinfunction "A_2") (pintype "passive"))
    )
    (net (code "5") (name "/C5") (class "Default")
      (node (ref "C8") (pin "2") (pinfunction "2_2") (pintype "passive"))
      (node (ref "R3") (pin "1") (pinfunction "1_1") (pintype "passive"))
      (node (ref "Z5") (pin "1") (pinfunction "K_1") (pintype "passive"))
      (node (ref "Z6") (pin "2") (pinfunction "A_2") (pintype "passive"))
    )
    (net (code "6") (name "/C6") (class "Default")
      (node (ref "C35") (pin "2") (pinfunction "2_2") (pintype "passive"))
      (node (ref "R66") (pin "1") (pinfunction "1_1") (pintype "passive"))
      (node (ref "Z6") (pin "1") (pinfunction "K_1") (pintype "passive"))
      (node (ref "Z7") (pin "2") (pinfunction "A_2") (pintype "passive"))
    )
    (net (code "7") (name "/C7") (class "Default")
      (node (ref "C31") (pin "2") (pinfunction "2_2") (pintype "passive"))
      (node (ref "R58") (pin "1") (pinfunction "1_1") (pintype "passive"))
      (node (ref "Z7") (pin "1") (pinfunction "K_1") (pintype "passive"))
      (node (ref "Z8") (pin "2") (pinfunction "A_2") (pintype "passive"))
    )
    (net (code "8") (name "/C8") (class "Default")
      (node (ref "C26") (pin "2") (pinfunction "2_2") (pintype "passive"))
      (node (ref "R44") (pin "1") (pinfunction "1_1") (pintype "passive"))
      (node (ref "Z8") (pin "1") (pinfunction "K_1") (pintype "passive"))
      (node (ref "Z9") (pin "2") (pinfunction "A_2") (pintype "passive"))
    )
    (net (code "9") (name "/C9") (class "Default")
      (node (ref "C17") (pin "2") (pinfunction "2_2") (pintype "passive"))
      (node (ref "R27") (pin "1") (pinfunction "1_1") (pintype "passive"))
      (node (ref "Z10") (pin "2") (pinfunction "A_2") (pintype "passive"))
      (node (ref "Z9") (pin "1") (pinfunction "K_1") (pintype "passive"))
    )
    (net (code "10") (name "/C10") (class "Default")
      (node (ref "C9") (pin "2") (pinfunction "2_2") (pintype "passive"))
      (node (ref "R4") (pin "1") (pinfunction "1_1") (pintype "passive"))
      (node (ref "Z10") (pin "1") (pinfunction "K_1") (pintype "passive"))
      (node (ref "Z11") (pin "2") (pinfunction "A_2") (pintype "passive"))
    )
    (net (code "11") (name "/C11") (class "Default")
      (node (ref "C36") (pin "2") (pinfunction "2_2") (pintype "passive"))
      (node (ref "R67") (pin "1") (pinfunction "1_1") (pintype "passive"))
      (node (ref "Z11") (pin "1") (pinfunction "K_1") (pintype "passive"))
      (node (ref "Z12") (pin "2") (pinfunction "A_2") (pintype "passive"))
    )
    (net (code "12") (name "/C12") (class "Default")
      (node (ref "C32") (pin "2") (pinfunction "2_2") (pintype "passive"))
      (node (ref "R59") (pin "1") (pinfunction "1_1") (pintype "passive"))
      (node (ref "Z12") (pin "1") (pinfunction "K_1") (pintype "passive"))
      (node (ref "Z13") (pin "2") (pinfunction "A_2") (pintype "passive"))
    )
    (net (code "13") (name "/C13") (class "Default")
      (node (ref "C27") (pin "2") (pinfunction "2_2") (pintype "passive"))
      (node (ref "R45") (pin "1") (pinfunction "1_1") (pintype "passive"))
      (node (ref "Z13") (pin "1") (pinfunction "K_1") (pintype "passive"))
      (node (ref "Z14") (pin "2") (pinfunction "A_2") (pintype "passive"))
    )
    (net (code "14") (name "/C14") (class "Default")
      (node (ref "C19") (pin "2") (pinfunction "2_2") (pintype "passive"))
      (node (ref "R28") (pin "1") (pinfunction "1_1") (pintype "passive"))
      (node (ref "Z14") (pin "1") (pinfunction "K_1") (pintype "passive"))
      (node (ref "Z15") (pin "2") (pinfunction "A_2") (pintype "passive"))
    )
    (net (code "15") (name "/C15") (class "Default")
      (node (ref "C10") (pin "2") (pinfunction "2_2") (pintype "passive"))
      (node (ref "R6") (pin "1") (pinfunction "1_1") (pintype "passive"))
      (node (ref "Z15") (pin "1") (pinfunction "K_1") (pintype "passive"))
      (node (ref "Z16") (pin "2") (pinfunction "A_2") (pintype "passive"))
    )
    (net (code "16") (name "/C16") (class "Default")
      (node (ref "C28") (pin "2") (pinfunction "2_2") (pintype "passive"))
      (node (ref "R47") (pin "1") (pinfunction "1_1") (pintype "passive"))
      (node (ref "Z16") (pin "1") (pinfunction "K_1") (pintype "passive"))
      (node (ref "Z17") (pin "2") (pinfunction "A_2") (pintype "passive"))
    )
    (net (code "17") (name "/C17") (class "Default")
      (node (ref "C20") (pin "2") (pinfunction "2_2") (pintype "passive"))
      (node (ref "R30") (pin "1") (pinfunction "1_1") (pintype "passive"))
      (node (ref "Z17") (pin "1") (pinfunction "K_1") (pintype "passive"))
      (node (ref "Z18") (pin "2") (pinfunction "A_2") (pintype "passive"))
    )
    (net (code "18") (name "/C18") (class "Default")
      (node (ref "C11") (pin "2") (pinfunction "2_2") (pintype "passive"))
      (node (ref "R7") (pin "1") (pinfunction "1_1") (pintype "passive"))
      (node (ref "Z18") (pin "1") (pinfunction "K_1") (pintype "passive"))
    )
    (net (code "19") (name "/Cell1") (class "Default")
      (node (ref "F1") (pin "1") (pinfunction "1_1") (pintype "passive"))
    )
    (net (code "20") (name "/Cell1_F") (class "Default")
      (node (ref "C0") (pin "2") (pinfunction "2_2") (pintype "passive"))
      (node (ref "C1") (pin "1") (pinfunction "1_1") (pintype "passive"))
      (node (ref "F1") (pin "2") (pinfunction "2_2") (pintype "passive"))
      (node (ref "LED2") (pin "1") (pinfunction "K_1") (pintype "passive"))
      (node (ref "Q1") (pin "2") (pinfunction "SOURCE_2") (pintype "passive"))
      (node (ref "R35") (pin "2") (pinfunction "2_2") (pintype "passive"))
      (node (ref "R38") (pin "2") (pinfunction "2_2") (pintype "passive"))
    )
    (net (code "21") (name "/Cell2") (class "Default")
      (node (ref "F2") (pin "1") (pinfunction "1_1") (pintype "passive"))
    )
    (net (code "22") (name "/Cell2_F") (class "Default")
      (node (ref "C1") (pin "2") (pinfunction "2_2") (pintype "passive"))
      (node (ref "C2") (pin "1") (pinfunction "1_1") (pintype "passive"))
      (node (ref "F2") (pin "2") (pinfunction "2_2") (pintype "passive"))
      (node (ref "LED3") (pin "1") (pinfunction "K_1") (pintype "passive"))
      (node (ref "Q2") (pin "2") (pinfunction "SOURCE_2") (pintype "passive"))
      (node (ref "R23") (pin "2") (pinfunction "2_2") (pintype "passive"))
      (node (ref "R26") (pin "2") (pinfunction "2_2") (pintype "passive"))
    )
    (net (code "23") (name "/Cell3") (class "Default")
      (node (ref "F3") (pin "1") (pinfunction "1_1") (pintype "passive"))
    )
    (net (code "24") (name "/Cell3_F") (class "Default")
      (node (ref "C2") (pin "2") (pinfunction "2_2") (pintype "passive"))
      (node (ref "C3") (pin "1") (pinfunction "1_1") (pintype "passive"))
      (node (ref "F3") (pin "2") (pinfunction "2_2") (pintype "passive"))
      (node (ref "LED4") (pin "1") (pinfunction "K_1") (pintype "passive"))
      (node (ref "Q3") (pin "2") (pinfunction "SOURCE_2") (pintype "passive"))
      (node (ref "R11") (pin "2") (pinfunction "2_2") (pintype "passive"))
      (node (ref "R14") (pin "2") (pinfunction "2_2") (pintype "passive"))
    )
    (net (code "25") (name "/Cell4") (class "Default")
      (node (ref "F4") (pin "1") (pinfunction "1_1") (pintype "passive"))
    )
    (net (code "26") (name "/Cell4_F") (class "Default")
      (node (ref "C3") (pin "2") (pinfunction "2_2") (pintype "passive"))
      (node (ref "C4") (pin "1") (pinfunction "1_1") (pintype "passive"))
      (node (ref "F4") (pin "2") (pinfunction "2_2") (pintype "passive"))
      (node (ref "LED5") (pin "1") (pinfunction "K_1") (pintype "passive"))
      (node (ref "Q4") (pin "2") (pinfunction "SOURCE_2") (pintype "passive"))
      (node (ref "R2") (pin "2") (pinfunction "2_2") (pintype "passive"))
      (node (ref "R21") (pin "2") (pinfunction "2_2") (pintype "passive"))
    )
    (net (code "27") (name "/Cell5") (class "Default")
      (node (ref "F5") (pin "1") (pinfunction "1_1") (pintype "passive"))
    )
    (net (code "28") (name "/Cell5_F") (class "Default")
      (node (ref "C33") (pin "1") (pinfunction "1_1") (pintype "passive"))
      (node (ref "C4") (pin "2") (pinfunction "2_2") (pintype "passive"))
      (node (ref "F5") (pin "2") (pinfunction "2_2") (pintype "passive"))
      (node (ref "LED6") (pin "1") (pinfunction "K_1") (pintype "passive"))
      (node (ref "Q5") (pin "2") (pinfunction "SOURCE_2") (pintype "passive"))
      (node (ref "R3") (pin "2") (pinfunction "2_2") (pintype "passive"))
      (node (ref "R72") (pin "2") (pinfunction "2_2") (pintype "passive"))
    )
    (net (code "29") (name "/Cell6") (class "Default")
      (node (ref "F6") (pin "1") (pinfunction "1_1") (pintype "passive"))
    )
    (net (code "30") (name "/Cell6_F") (class "Default")
      (node (ref "C29") (pin "1") (pinfunction "1_1") (pintype "passive"))
      (node (ref "C33") (pin "2") (pinfunction "2_2") (pintype "passive"))
      (node (ref "F6") (pin "2") (pinfunction "2_2") (pintype "passive"))
      (node (ref "LED7") (pin "1") (pinfunction "K_1") (pintype "passive"))
      (node (ref "Q6") (pin "2") (pinfunction "SOURCE_2") (pintype "passive"))
      (node (ref "R64") (pin "2") (pinfunction "2_2") (pintype "passive"))
      (node (ref "R66") (pin "2") (pinfunction "2_2") (pintype "passive"))
    )
    (net (code "31") (name "/Cell7") (class "Default")
      (node (ref "F7") (pin "1") (pinfunction "1_1") (pintype "passive"))
    )
    (net (code "32") (name "/Cell7_F") (class "Default")
      (node (ref "C23") (pin "1") (pinfunction "1_1") (pintype "passive"))
      (node (ref "C29") (pin "2") (pinfunction "2_2") (pintype "passive"))
      (node (ref "F7") (pin "2") (pinfunction "2_2") (pintype "passive"))
      (node (ref "LED8") (pin "1") (pinfunction "K_1") (pintype "passive"))
      (node (ref "Q7") (pin "2") (pinfunction "SOURCE_2") (pintype "passive"))
      (node (ref "R55") (pin "2") (pinfunction "2_2") (pintype "passive"))
      (node (ref "R58") (pin "2") (pinfunction "2_2") (pintype "passive"))
    )
    (net (code "33") (name "/Cell8") (class "Default")
      (node (ref "F8") (pin "1") (pinfunction "1_1") (pintype "passive"))
    )
    (net (code "34") (name "/Cell8_F") (class "Default")
      (node (ref "C14") (pin "1") (pinfunction "1_1") (pintype "passive"))
      (node (ref "C23") (pin "2") (pinfunction "2_2") (pintype "passive"))
      (node (ref "F8") (pin "2") (pinfunction "2_2") (pintype "passive"))
      (node (ref "LED9") (pin "1") (pinfunction "K_1") (pintype "passive"))
      (node (ref "Q8") (pin "2") (pinfunction "SOURCE_2") (pintype "passive"))
      (node (ref "R40") (pin "2") (pinfunction "2_2") (pintype "passive"))
      (node (ref "R44") (pin "2") (pinfunction "2_2") (pintype "passive"))
    )
    (net (code "35") (name "/Cell9") (class "Default")
      (node (ref "F9") (pin "1") (pinfunction "1_1") (pintype "passive"))
    )
    (net (code "36") (name "/Cell9_F") (class "Default")
      (node (ref "C14") (pin "2") (pinfunction "2_2") (pintype "passive"))
      (node (ref "C5") (pin "1") (pinfunction "1_1") (pintype "passive"))
      (node (ref "F9") (pin "2") (pinfunction "2_2") (pintype "passive"))
      (node (ref "LED10") (pin "1") (pinfunction "K_1") (pintype "passive"))
      (node (ref "Q9") (pin "2") (pinfunction "SOURCE_2") (pintype "passive"))
      (node (ref "R22") (pin "2") (pinfunction "2_2") (pintype "passive"))
      (node (ref "R27") (pin "2") (pinfunction "2_2") (pintype "passive"))
    )
    (net (code "37") (name "/Cell10") (class "Default")
      (node (ref "F10") (pin "1") (pinfunction "1_1") (pintype "passive"))
    )
    (net (code "38") (name "/Cell10_F") (class "Default")
      (node (ref "C34") (pin "1") (pinfunction "1_1") (pintype "passive"))
      (node (ref "C5") (pin "2") (pinfunction "2_2") (pintype "passive"))
      (node (ref "F10") (pin "2") (pinfunction "2_2") (pintype "passive"))
      (node (ref "LED11") (pin "1") (pinfunction "K_1") (pintype "passive"))
      (node (ref "Q10") (pin "2") (pinfunction "SOURCE_2") (pintype "passive"))
      (node (ref "R4") (pin "2") (pinfunction "2_2") (pintype "passive"))
      (node (ref "R73") (pin "2") (pinfunction "2_2") (pintype "passive"))
    )
    (net (code "39") (name "/Cell11") (class "Default")
      (node (ref "F11") (pin "1") (pinfunction "1_1") (pintype "passive"))
    )
    (net (code "40") (name "/Cell11_F") (class "Default")
      (node (ref "C30") (pin "1") (pinfunction "1_1") (pintype "passive"))
      (node (ref "C34") (pin "2") (pinfunction "2_2") (pintype "passive"))
      (node (ref "F11") (pin "2") (pinfunction "2_2") (pintype "passive"))
      (node (ref "LED12") (pin "1") (pinfunction "K_1") (pintype "passive"))
      (node (ref "Q11") (pin "2") (pinfunction "SOURCE_2") (pintype "passive"))
      (node (ref "R65") (pin "2") (pinfunction "2_2") (pintype "passive"))
      (node (ref "R67") (pin "2") (pinfunction "2_2") (pintype "passive"))
    )
    (net (code "41") (name "/Cell12") (class "Default")
      (node (ref "F12") (pin "1") (pinfunction "1_1") (pintype "passive"))
    )
    (net (code "42") (name "/Cell12_F") (class "Default")
      (node (ref "C25") (pin "1") (pinfunction "1_1") (pintype "passive"))
      (node (ref "C30") (pin "2") (pinfunction "2_2") (pintype "passive"))
      (node (ref "F12") (pin "2") (pinfunction "2_2") (pintype "passive"))
      (node (ref "LED13") (pin "1") (pinfunction "K_1") (pintype "passive"))
      (node (ref "Q12") (pin "2") (pinfunction "SOURCE_2") (pintype "passive"))
      (node (ref "R56") (pin "2") (pinfunction "2_2") (pintype "passive"))
      (node (ref "R59") (pin "2") (pinfunction "2_2") (pintype "passive"))
    )
    (net (code "43") (name "/Cell13") (class "Default")
      (node (ref "F13") (pin "1") (pinfunction "1_1") (pintype "passive"))
    )
    (net (code "44") (name "/Cell13_F") (class "Default")
      (node (ref "C16") (pin "1") (pinfunction "1_1") (pintype "passive"))
      (node (ref "C25") (pin "2") (pinfunction "2_2") (pintype "passive"))
      (node (ref "F13") (pin "2") (pinfunction "2_2") (pintype "passive"))
      (node (ref "LED14") (pin "1") (pinfunction "K_1") (pintype "passive"))
      (node (ref "Q13") (pin "2") (pinfunction "SOURCE_2") (pintype "passive"))
      (node (ref "R41") (pin "2") (pinfunction "2_2") (pintype "passive"))
      (node (ref "R45") (pin "2") (pinfunction "2_2") (pintype "passive"))
    )
    (net (code "45") (name "/Cell14") (class "Default")
      (node (ref "F14") (pin "1") (pinfunction "1_1") (pintype "passive"))
    )
    (net (code "46") (name "/Cell14_F") (class "Default")
      (node (ref "C16") (pin "2") (pinfunction "2_2") (pintype "passive"))
      (node (ref "C6") (pin "1") (pinfunction "1_1") (pintype "passive"))
      (node (ref "F14") (pin "2") (pinfunction "2_2") (pintype "passive"))
      (node (ref "LED15") (pin "1") (pinfunction "K_1") (pintype "passive"))
      (node (ref "Q14") (pin "2") (pinfunction "SOURCE_2") (pintype "passive"))
      (node (ref "R24") (pin "2") (pinfunction "2_2") (pintype "passive"))
      (node (ref "R28") (pin "2") (pinfunction "2_2") (pintype "passive"))
    )
    (net (code "47") (name "/Cell15") (class "Default")
      (node (ref "F15") (pin "1") (pinfunction "1_1") (pintype "passive"))
    )
    (net (code "48") (name "/Cell15_F") (class "Default")
      (node (ref "C22") (pin "1") (pinfunction "1_1") (pintype "passive"))
      (node (ref "C6") (pin "2") (pinfunction "2_2") (pintype "passive"))
      (node (ref "F15") (pin "2") (pinfunction "2_2") (pintype "passive"))
      (node (ref "LED16") (pin "1") (pinfunction "K_1") (pintype "passive"))
      (node (ref "Q15") (pin "2") (pinfunction "SOURCE_2") (pintype "passive"))
      (node (ref "R57") (pin "2") (pinfunction "2_2") (pintype "passive"))
      (node (ref "R6") (pin "2") (pinfunction "2_2") (pintype "passive"))
    )
    (net (code "49") (name "/Cell16") (class "Default")
      (node (ref "F16") (pin "1") (pinfunction "1_1") (pintype "passive"))
    )
    (net (code "50") (name "/Cell16_F") (class "Default")
      (node (ref "C13") (pin "1") (pinfunction "1_1") (pintype "passive"))
      (node (ref "C22") (pin "2") (pinfunction "2_2") (pintype "passive"))
      (node (ref "F16") (pin "2") (pinfunction "2_2") (pintype "passive"))
      (node (ref "LED17") (pin "1") (pinfunction "K_1") (pintype "passive"))
      (node (ref "Q16") (pin "2") (pinfunction "SOURCE_2") (pintype "passive"))
      (node (ref "R42") (pin "2") (pinfunction "2_2") (pintype "passive"))
      (node (ref "R47") (pin "2") (pinfunction "2_2") (pintype "passive"))
    )
    (net (code "51") (name "/Cell17") (class "Default")
      (node (ref "F17") (pin "1") (pinfunction "1_1") (pintype "passive"))
    )
    (net (code "52") (name "/Cell17_F") (class "Default")
      (node (ref "C13") (pin "2") (pinfunction "2_2") (pintype "passive"))
      (node (ref "C7") (pin "1") (pinfunction "1_1") (pintype "passive"))
      (node (ref "F17") (pin "2") (pinfunction "2_2") (pintype "passive"))
      (node (ref "LED18") (pin "1") (pinfunction "K_1") (pintype "passive"))
      (node (ref "Q17") (pin "2") (pinfunction "SOURCE_2") (pintype "passive"))
      (node (ref "R25") (pin "2") (pinfunction "2_2") (pintype "passive"))
      (node (ref "R30") (pin "2") (pinfunction "2_2") (pintype "passive"))
    )
    (net (code "53") (name "/Cell18") (class "Default")
      (node (ref "F18") (pin "1") (pinfunction "1_1") (pintype "passive"))
    )
    (net (code "54") (name "/Cell18_F") (class "Default")
      (node (ref "C7") (pin "2") (pinfunction "2_2") (pintype "passive"))
      (node (ref "F18") (pin "2") (pinfunction "2_2") (pintype "passive"))
      (node (ref "Q18") (pin "2") (pinfunction "SOURCE_2") (pintype "passive"))
      (node (ref "R7") (pin "2") (pinfunction "2_2") (pintype "passive"))
    )
    (net (code "55") (name "/S1") (class "Default")
      (node (ref "R1") (pin "1") (pinfunction "1_1") (pintype "passive"))
    )
    (net (code "56") (name "/S2") (class "Default")
      (node (ref "R29") (pin "1") (pinfunction "1_1") (pintype "passive"))
    )
    (net (code "57") (name "/S3") (class "Default")
      (node (ref "R17") (pin "1") (pinfunction "1_1") (pintype "passive"))
    )
    (net (code "58") (name "/S4") (class "Default")
      (node (ref "R5") (pin "1") (pinfunction "1_1") (pintype "passive"))
    )
    (net (code "59") (name "/S5") (class "Default")
      (node (ref "R9") (pin "1") (pinfunction "1_1") (pintype "passive"))
    )
    (net (code "60") (name "/S6") (class "Default")
      (node (ref "R68") (pin "1") (pinfunction "1_1") (pintype "passive"))
    )
    (net (code "61") (name "/S7") (class "Default")
      (node (ref "R60") (pin "1") (pinfunction "1_1") (pintype "passive"))
    )
    (net (code "62") (name "/S8") (class "Default")
      (node (ref "R48") (pin "1") (pinfunction "1_1") (pintype "passive"))
    )
    (net (code "63") (name "/S9") (class "Default")
      (node (ref "R31") (pin "1") (pinfunction "1_1") (pintype "passive"))
    )
    (net (code "64") (name "/S10") (class "Default")
      (node (ref "R10") (pin "1") (pinfunction "1_1") (pintype "passive"))
    )
    (net (code "65") (name "/S11") (class "Default")
      (node (ref "R69") (pin "1") (pinfunction "1_1") (pintype "passive"))
    )
    (net (code "66") (name "/S12") (class "Default")
      (node (ref "R61") (pin "1") (pinfunction "1_1") (pintype "passive"))
    )
    (net (code "67") (name "/S13") (class "Default")
      (node (ref "R50") (pin "1") (pinfunction "1_1") (pintype "passive"))
    )
    (net (code "68") (name "/S14") (class "Default")
      (node (ref "R33") (pin "1") (pinfunction "1_1") (pintype "passive"))
    )
    (net (code "69") (name "/S15") (class "Default")
      (node (ref "R12") (pin "1") (pinfunction "1_1") (pintype "passive"))
    )
    (net (code "70") (name "/S16") (class "Default")
      (node (ref "R51") (pin "1") (pinfunction "1_1") (pintype "passive"))
    )
    (net (code "71") (name "/S17") (class "Default")
      (node (ref "R34") (pin "1") (pinfunction "1_1") (pintype "passive"))
    )
    (net (code "72") (name "/S18") (class "Default")
      (node (ref "R13") (pin "1") (pinfunction "1_1") (pintype "passive"))
    )
    (net (code "73") (name "GND") (class "Default")
      (node (ref "C0") (pin "1") (pinfunction "1_1") (pintype "passive"))
      (node (ref "C10") (pin "1") (pinfunction "1_1") (pintype "passive"))
      (node (ref "C11") (pin "1") (pinfunction "1_1") (pintype "passive"))
      (node (ref "C12") (pin "1") (pinfunction "1_1") (pintype "passive"))
      (node (ref "C15") (pin "1") (pinfunction "1_1") (pintype "passive"))
      (node (ref "C17") (pin "1") (pinfunction "1_1") (pintype "passive"))
      (node (ref "C18") (pin "1") (pinfunction "1_1") (pintype "passive"))
      (node (ref "C19") (pin "1") (pinfunction "1_1") (pintype "passive"))
      (node (ref "C20") (pin "1") (pinfunction "1_1") (pintype "passive"))
      (node (ref "C21") (pin "1") (pinfunction "1_1") (pintype "passive"))
      (node (ref "C26") (pin "1") (pinfunction "1_1") (pintype "passive"))
      (node (ref "C27") (pin "1") (pinfunction "1_1") (pintype "passive"))
      (node (ref "C28") (pin "1") (pinfunction "1_1") (pintype "passive"))
      (node (ref "C31") (pin "1") (pinfunction "1_1") (pintype "passive"))
      (node (ref "C32") (pin "1") (pinfunction "1_1") (pintype "passive"))
      (node (ref "C35") (pin "1") (pinfunction "1_1") (pintype "passive"))
      (node (ref "C36") (pin "1") (pinfunction "1_1") (pintype "passive"))
      (node (ref "C8") (pin "1") (pinfunction "1_1") (pintype "passive"))
      (node (ref "C9") (pin "1") (pinfunction "1_1") (pintype "passive"))
      (node (ref "LED1") (pin "1") (pinfunction "K_1") (pintype "passive"))
      (node (ref "R46") (pin "2") (pinfunction "2_2") (pintype "passive"))
      (node (ref "Z1") (pin "2") (pinfunction "A_2") (pintype "passive"))
    )
    (net (code "74") (name "Net-(LED1-A)") (class "Default")
      (node (ref "LED1") (pin "2") (pinfunction "A_2") (pintype "passive"))
      (node (ref "R43") (pin "2") (pinfunction "2_2") (pintype "passive"))
    )
    (net (code "75") (name "Net-(LED2-A)") (class "Default")
      (node (ref "LED2") (pin "2") (pinfunction "A_2") (pintype "passive"))
      (node (ref "R32") (pin "2") (pinfunction "2_2") (pintype "passive"))
    )
    (net (code "76") (name "Net-(LED3-A)") (class "Default")
      (node (ref "LED3") (pin "2") (pinfunction "A_2") (pintype "passive"))
      (node (ref "R20") (pin "2") (pinfunction "2_2") (pintype "passive"))
    )
    (net (code "77") (name "Net-(LED4-A)") (class "Default")
      (node (ref "LED4") (pin "2") (pinfunction "A_2") (pintype "passive"))
      (node (ref "R8") (pin "2") (pinfunction "2_2") (pintype "passive"))
    )
    (net (code "78") (name "Net-(LED5-A)") (class "Default")
      (node (ref "LED5") (pin "2") (pinfunction "A_2") (pintype "passive"))
      (node (ref "R15") (pin "2") (pinfunction "2_2") (pintype "passive"))
    )
    (net (code "79") (name "Net-(LED6-A)") (class "Default")
      (node (ref "LED6") (pin "2") (pinfunction "A_2") (pintype "passive"))
      (node (ref "R70") (pin "2") (pinfunction "2_2") (pintype "passive"))
    )
    (net (code "80") (name "Net-(LED7-A)") (class "Default")
      (node (ref "LED7") (pin "2") (pinfunction "A_2") (pintype "passive"))
      (node (ref "R62") (pin "2") (pinfunction "2_2") (pintype "passive"))
    )
    (net (code "81") (name "Net-(LED8-A)") (class "Default")
      (node (ref "LED8") (pin "2") (pinfunction "A_2") (pintype "passive"))
      (node (ref "R52") (pin "2") (pinfunction "2_2") (pintype "passive"))
    )
    (net (code "82") (name "Net-(LED9-A)") (class "Default")
      (node (ref "LED9") (pin "2") (pinfunction "A_2") (pintype "passive"))
      (node (ref "R36") (pin "2") (pinfunction "2_2") (pintype "passive"))
    )
    (net (code "83") (name "Net-(LED10-A)") (class "Default")
      (node (ref "LED10") (pin "2") (pinfunction "A_2") (pintype "passive"))
      (node (ref "R16") (pin "2") (pinfunction "2_2") (pintype "passive"))
    )
    (net (code "84") (name "Net-(LED11-A)") (class "Default")
      (node (ref "LED11") (pin "2") (pinfunction "A_2") (pintype "passive"))
      (node (ref "R71") (pin "2") (pinfunction "2_2") (pintype "passive"))
    )
    (net (code "85") (name "Net-(LED12-A)") (class "Default")
      (node (ref "LED12") (pin "2") (pinfunction "A_2") (pintype "passive"))
      (node (ref "R63") (pin "2") (pinfunction "2_2") (pintype "passive"))
    )
    (net (code "86") (name "Net-(LED13-A)") (class "Default")
      (node (ref "LED13") (pin "2") (pinfunction "A_2") (pintype "passive"))
      (node (ref "R53") (pin "2") (pinfunction "2_2") (pintype "passive"))
    )
    (net (code "87") (name "Net-(LED14-A)") (class "Default")
      (node (ref "LED14") (pin "2") (pinfunction "A_2") (pintype "passive"))
      (node (ref "R37") (pin "2") (pinfunction "2_2") (pintype "passive"))
    )
    (net (code "88") (name "Net-(LED15-A)") (class "Default")
      (node (ref "LED15") (pin "2") (pinfunction "A_2") (pintype "passive"))
      (node (ref "R18") (pin "2") (pinfunction "2_2") (pintype "passive"))
    )
    (net (code "89") (name "Net-(LED16-A)") (class "Default")
      (node (ref "LED16") (pin "2") (pinfunction "A_2") (pintype "passive"))
      (node (ref "R54") (pin "2") (pinfunction "2_2") (pintype "passive"))
    )
    (net (code "90") (name "Net-(LED17-A)") (class "Default")
      (node (ref "LED17") (pin "2") (pinfunction "A_2") (pintype "passive"))
      (node (ref "R39") (pin "2") (pinfunction "2_2") (pintype "passive"))
    )
    (net (code "91") (name "Net-(LED18-A)") (class "Default")
      (node (ref "LED18") (pin "2") (pinfunction "A_2") (pintype "passive"))
      (node (ref "R19") (pin "2") (pinfunction "2_2") (pintype "passive"))
    )
    (net (code "92") (name "Net-(Q1-DRAIN)") (class "Default")
      (node (ref "Q1") (pin "3") (pinfunction "DRAIN_3") (pintype "passive"))
      (node (ref "R43") (pin "1") (pinfunction "1_1") (pintype "passive"))
      (node (ref "R46") (pin "1") (pinfunction "1_1") (pintype "passive"))
    )
    (net (code "93") (name "Net-(Q1-GATE)") (class "Default")
      (node (ref "Q1") (pin "1") (pinfunction "GATE_1") (pintype "passive"))
      (node (ref "R1") (pin "2") (pinfunction "2_2") (pintype "passive"))
    )
    (net (code "94") (name "Net-(Q2-DRAIN)") (class "Default")
      (node (ref "Q2") (pin "3") (pinfunction "DRAIN_3") (pintype "passive"))
      (node (ref "R32") (pin "1") (pinfunction "1_1") (pintype "passive"))
      (node (ref "R35") (pin "1") (pinfunction "1_1") (pintype "passive"))
    )
    (net (code "95") (name "Net-(Q2-GATE)") (class "Default")
      (node (ref "Q2") (pin "1") (pinfunction "GATE_1") (pintype "passive"))
      (node (ref "R29") (pin "2") (pinfunction "2_2") (pintype "passive"))
    )
    (net (code "96") (name "Net-(Q3-DRAIN)") (class "Default")
      (node (ref "Q3") (pin "3") (pinfunction "DRAIN_3") (pintype "passive"))
      (node (ref "R20") (pin "1") (pinfunction "1_1") (pintype "passive"))
      (node (ref "R23") (pin "1") (pinfunction "1_1") (pintype "passive"))
    )
    (net (code "97") (name "Net-(Q3-GATE)") (class "Default")
      (node (ref "Q3") (pin "1") (pinfunction "GATE_1") (pintype "passive"))
      (node (ref "R17") (pin "2") (pinfunction "2_2") (pintype "passive"))
    )
    (net (code "98") (name "Net-(Q4-DRAIN)") (class "Default")
      (node (ref "Q4") (pin "3") (pinfunction "DRAIN_3") (pintype "passive"))
      (node (ref "R11") (pin "1") (pinfunction "1_1") (pintype "passive"))
      (node (ref "R8") (pin "1") (pinfunction "1_1") (pintype "passive"))
    )
    (net (code "99") (name "Net-(Q4-GATE)") (class "Default")
      (node (ref "Q4") (pin "1") (pinfunction "GATE_1") (pintype "passive"))
      (node (ref "R5") (pin "2") (pinfunction "2_2") (pintype "passive"))
    )
    (net (code "100") (name "Net-(Q5-DRAIN)") (class "Default")
      (node (ref "Q5") (pin "3") (pinfunction "DRAIN_3") (pintype "passive"))
      (node (ref "R15") (pin "1") (pinfunction "1_1") (pintype "passive"))
      (node (ref "R21") (pin "1") (pinfunction "1_1") (pintype "passive"))
    )
    (net (code "101") (name "Net-(Q5-GATE)") (class "Default")
      (node (ref "Q5") (pin "1") (pinfunction "GATE_1") (pintype "passive"))
      (node (ref "R9") (pin "2") (pinfunction "2_2") (pintype "passive"))
    )
    (net (code "102") (name "Net-(Q6-DRAIN)") (class "Default")
      (node (ref "Q6") (pin "3") (pinfunction "DRAIN_3") (pintype "passive"))
      (node (ref "R70") (pin "1") (pinfunction "1_1") (pintype "passive"))
      (node (ref "R72") (pin "1") (pinfunction "1_1") (pintype "passive"))
    )
    (net (code "103") (name "Net-(Q6-GATE)") (class "Default")
      (node (ref "Q6") (pin "1") (pinfunction "GATE_1") (pintype "passive"))
      (node (ref "R68") (pin "2") (pinfunction "2_2") (pintype "passive"))
    )
    (net (code "104") (name "Net-(Q7-DRAIN)") (class "Default")
      (node (ref "Q7") (pin "3") (pinfunction "DRAIN_3") (pintype "passive"))
      (node (ref "R62") (pin "1") (pinfunction "1_1") (pintype "passive"))
      (node (ref "R64") (pin "1") (pinfunction "1_1") (pintype "passive"))
    )
    (net (code "105") (name "Net-(Q7-GATE)") (class "Default")
      (node (ref "Q7") (pin "1") (pinfunction "GATE_1") (pintype "passive"))
      (node (ref "R60") (pin "2") (pinfunction "2_2") (pintype "passive"))
    )
    (net (code "106") (name "Net-(Q8-DRAIN)") (class "Default")
      (node (ref "Q8") (pin "3") (pinfunction "DRAIN_3") (pintype "passive"))
      (node (ref "R52") (pin "1") (pinfunction "1_1") (pintype "passive"))
      (node (ref "R55") (pin "1") (pinfunction "1_1") (pintype "passive"))
    )
    (net (code "107") (name "Net-(Q8-GATE)") (class "Default")
      (node (ref "Q8") (pin "1") (pinfunction "GATE_1") (pintype "passive"))
      (node (ref "R48") (pin "2") (pinfunction "2_2") (pintype "passive"))
    )
    (net (code "108") (name "Net-(Q9-DRAIN)") (class "Default")
      (node (ref "Q9") (pin "3") (pinfunction "DRAIN_3") (pintype "passive"))
      (node (ref "R36") (pin "1") (pinfunction "1_1") (pintype "passive"))
      (node (ref "R40") (pin "1") (pinfunction "1_1") (pintype "passive"))
    )
    (net (code "109") (name "Net-(Q9-GATE)") (class "Default")
      (node (ref "Q9") (pin "1") (pinfunction "GATE_1") (pintype "passive"))
      (node (ref "R31") (pin "2") (pinfunction "2_2") (pintype "passive"))
    )
    (net (code "110") (name "Net-(Q10-DRAIN)") (class "Default")
      (node (ref "Q10") (pin "3") (pinfunction "DRAIN_3") (pintype "passive"))
      (node (ref "R16") (pin "1") (pinfunction "1_1") (pintype "passive"))
      (node (ref "R22") (pin "1") (pinfunction "1_1") (pintype "passive"))
    )
    (net (code "111") (name "Net-(Q10-GATE)") (class "Default")
      (node (ref "Q10") (pin "1") (pinfunction "GATE_1") (pintype "passive"))
      (node (ref "R10") (pin "2") (pinfunction "2_2") (pintype "passive"))
    )
    (net (code "112") (name "Net-(Q11-DRAIN)") (class "Default")
      (node (ref "Q11") (pin "3") (pinfunction "DRAIN_3") (pintype "passive"))
      (node (ref "R71") (pin "1") (pinfunction "1_1") (pintype "passive"))
      (node (ref "R73") (pin "1") (pinfunction "1_1") (pintype "passive"))
    )
    (net (code "113") (name "Net-(Q11-GATE)") (class "Default")
      (node (ref "Q11") (pin "1") (pinfunction "GATE_1") (pintype "passive"))
      (node (ref "R69") (pin "2") (pinfunction "2_2") (pintype "passive"))
    )
    (net (code "114") (name "Net-(Q12-DRAIN)") (class "Default")
      (node (ref "Q12") (pin "3") (pinfunction "DRAIN_3") (pintype "passive"))
      (node (ref "R63") (pin "1") (pinfunction "1_1") (pintype "passive"))
      (node (ref "R65") (pin "1") (pinfunction "1_1") (pintype "passive"))
    )
    (net (code "115") (name "Net-(Q12-GATE)") (class "Default")
      (node (ref "Q12") (pin "1") (pinfunction "GATE_1") (pintype "passive"))
      (node (ref "R61") (pin "2") (pinfunction "2_2") (pintype "passive"))
    )
    (net (code "116") (name "Net-(Q13-DRAIN)") (class "Default")
      (node (ref "Q13") (pin "3") (pinfunction "DRAIN_3") (pintype "passive"))
      (node (ref "R53") (pin "1") (pinfunction "1_1") (pintype "passive"))
      (node (ref "R56") (pin "1") (pinfunction "1_1") (pintype "passive"))
    )
    (net (code "117") (name "Net-(Q13-GATE)") (class "Default")
      (node (ref "Q13") (pin "1") (pinfunction "GATE_1") (pintype "passive"))
      (node (ref "R50") (pin "2") (pinfunction "2_2") (pintype "passive"))
    )
    (net (code "118") (name "Net-(Q14-DRAIN)") (class "Default")
      (node (ref "Q14") (pin "3") (pinfunction "DRAIN_3") (pintype "passive"))
      (node (ref "R37") (pin "1") (pinfunction "1_1") (pintype "passive"))
      (node (ref "R41") (pin "1") (pinfunction "1_1") (pintype "passive"))
    )
    (net (code "119") (name "Net-(Q14-GATE)") (class "Default")
      (node (ref "Q14") (pin "1") (pinfunction "GATE_1") (pintype "passive"))
      (node (ref "R33") (pin "2") (pinfunction "2_2") (pintype "passive"))
    )
    (net (code "120") (name "Net-(Q15-DRAIN)") (class "Default")
      (node (ref "Q15") (pin "3") (pinfunction "DRAIN_3") (pintype "passive"))
      (node (ref "R18") (pin "1") (pinfunction "1_1") (pintype "passive"))
      (node (ref "R24") (pin "1") (pinfunction "1_1") (pintype "passive"))
    )
    (net (code "121") (name "Net-(Q15-GATE)") (class "Default")
      (node (ref "Q15") (pin "1") (pinfunction "GATE_1") (pintype "passive"))
      (node (ref "R12") (pin "2") (pinfunction "2_2") (pintype "passive"))
    )
    (net (code "122") (name "Net-(Q16-DRAIN)") (class "Default")
      (node (ref "Q16") (pin "3") (pinfunction "DRAIN_3") (pintype "passive"))
      (node (ref "R54") (pin "1") (pinfunction "1_1") (pintype "passive"))
      (node (ref "R57") (pin "1") (pinfunction "1_1") (pintype "passive"))
    )
    (net (code "123") (name "Net-(Q16-GATE)") (class "Default")
      (node (ref "Q16") (pin "1") (pinfunction "GATE_1") (pintype "passive"))
      (node (ref "R51") (pin "2") (pinfunction "2_2") (pintype "passive"))
    )
    (net (code "124") (name "Net-(Q17-DRAIN)") (class "Default")
      (node (ref "Q17") (pin "3") (pinfunction "DRAIN_3") (pintype "passive"))
      (node (ref "R39") (pin "1") (pinfunction "1_1") (pintype "passive"))
      (node (ref "R42") (pin "1") (pinfunction "1_1") (pintype "passive"))
    )
    (net (code "125") (name "Net-(Q17-GATE)") (class "Default")
      (node (ref "Q17") (pin "1") (pinfunction "GATE_1") (pintype "passive"))
      (node (ref "R34") (pin "2") (pinfunction "2_2") (pintype "passive"))
    )
    (net (code "126") (name "Net-(Q18-DRAIN)") (class "Default")
      (node (ref "Q18") (pin "3") (pinfunction "DRAIN_3") (pintype "passive"))
      (node (ref "R19") (pin "1") (pinfunction "1_1") (pintype "passive"))
      (node (ref "R25") (pin "1") (pinfunction "1_1") (pintype "passive"))
    )
    (net (code "127") (name "Net-(Q18-GATE)") (class "Default")
      (node (ref "Q18") (pin "1") (pinfunction "GATE_1") (pintype "passive"))
      (node (ref "R13") (pin "2") (pinfunction "2_2") (pintype "passive"))
    )
  )
)
